# T35_8_CONNECTORS.net
KiCad netlist of a schematic drawn in Altium Designer
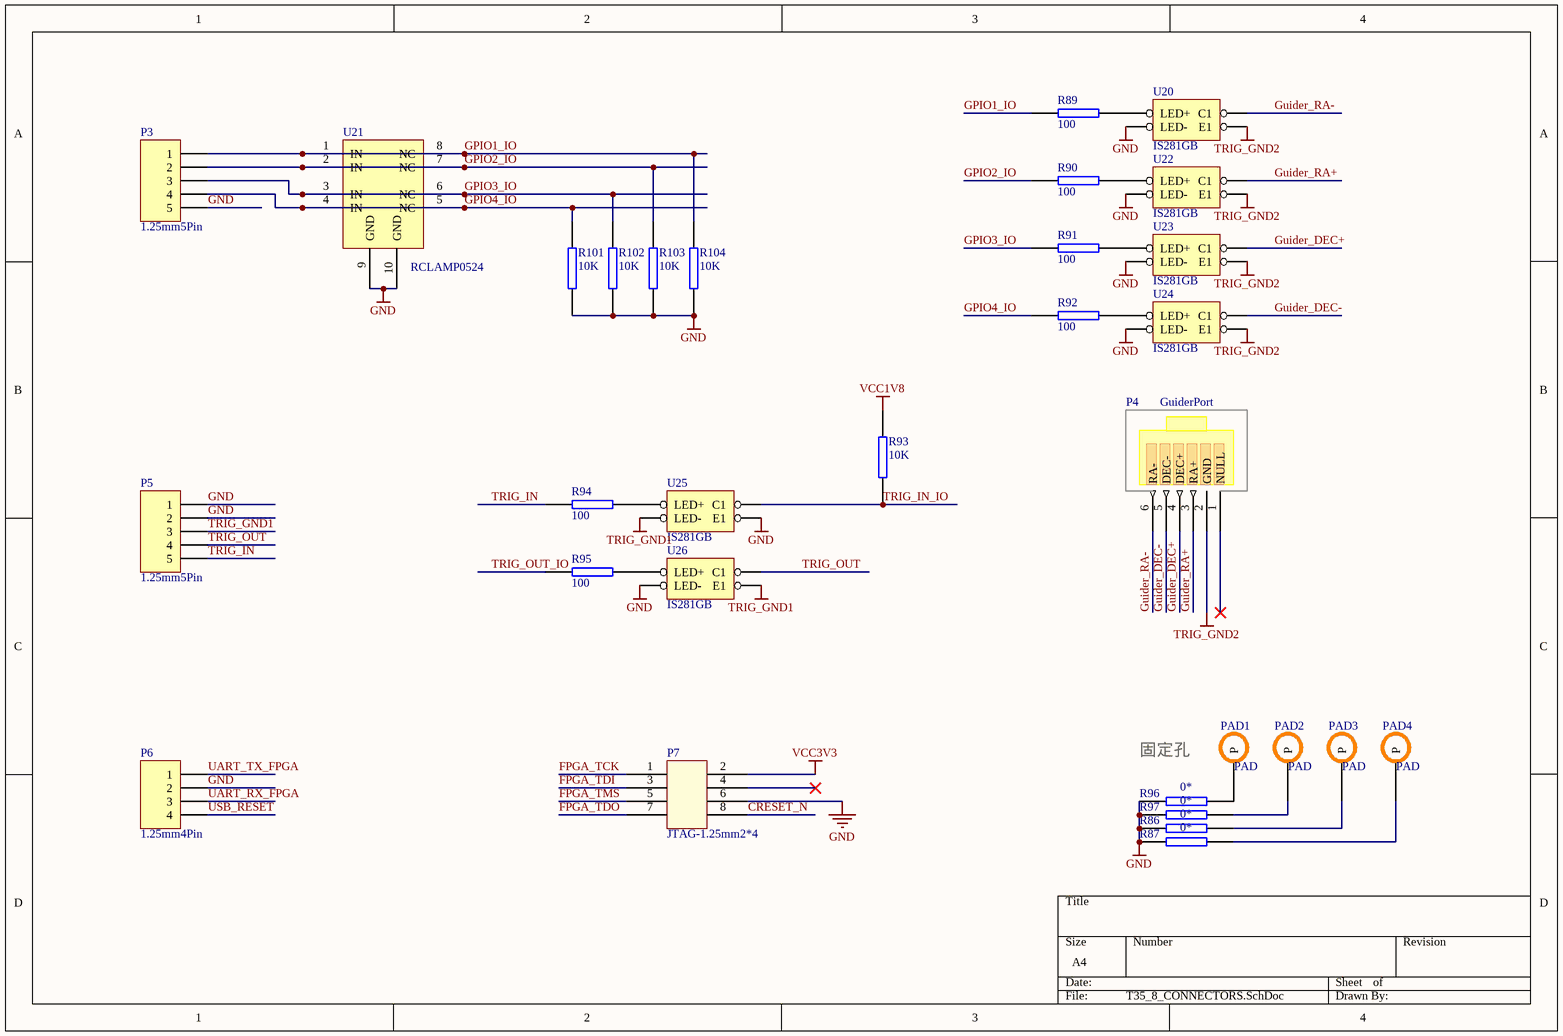
[diagram p0: T35_8_CONNECTORS.SchDoc]

(export (version "E")
  (design (tool "Eeschema 10.0.6"))
  (components
    (comp (ref "P3")
      (value "1.25mm5Pin")
      (footprint "CC125-5")
      (description "1.25mm间距5Pin插座")
      (fields (field (name "PUBLISHER") "Altium Limited"))
      (libsource (lib "Miscellaneous Connectors") (part "Header 5"))
    )
    (comp (ref "P4")
      (value "GuiderPort")
      (footprint "RJ11-SMD")
      (description "导星口RJ11")
      (libsource (lib "T35-V2") (part "GuiderPort"))
    )
    (comp (ref "P5")
      (value "1.25mm5Pin")
      (footprint "CC125-5")
      (description "1.25mm间距5Pin插座")
      (fields (field (name "PUBLISHER") "Altium Limited"))
      (libsource (lib "Miscellaneous Connectors") (part "Header 5"))
    )
    (comp (ref "P6")
      (value "1.25mm4Pin")
      (footprint "CON_530470410_MOL")
      (description "1.25mm间距4Pin插座")
      (libsource (lib "T35") (part "Con_4"))
    )
    (comp (ref "P7")
      (value "JTAG-1.25mm2*4")
      (footprint "MHDR2X4")
      (description "1.25mm间距2*4 8PinJTAG烧写座")
      (libsource (lib "T35-V2") (part "1.27mm2*4JTAGSocket"))
    )
    (comp (ref "PAD1")
      (value "PAD")
      (footprint "M2-R4-NC")
      (description "固定孔")
      (libsource (lib "QHY_LIB_SCH_AD10") (part "PAD"))
    )
    (comp (ref "PAD2")
      (value "PAD")
      (footprint "M2-R4-NC")
      (description "固定孔")
      (libsource (lib "QHY_LIB_SCH_AD10") (part "PAD"))
    )
    (comp (ref "PAD3")
      (value "PAD")
      (footprint "M1.6-R3.2-NC")
      (description "固定孔")
      (libsource (lib "QHY_LIB_SCH_AD10") (part "PAD"))
    )
    (comp (ref "PAD4")
      (value "PAD")
      (footprint "M1.6-R3.2-NC")
      (description "固定孔")
      (libsource (lib "QHY_LIB_SCH_AD10") (part "PAD"))
    )
    (comp (ref "R86")
      (value "0*")
      (footprint "0402RS")
      (description "贴片电阻")
      (libsource (lib "*") (part "RES2"))
    )
    (comp (ref "R87")
      (value "0*")
      (footprint "0402RS")
      (description "贴片电阻")
      (libsource (lib "*") (part "RES2"))
    )
    (comp (ref "R89")
      (value "100")
      (footprint "0402RS")
      (description "贴片电阻")
      (libsource (lib "*") (part "RES2"))
    )
    (comp (ref "R90")
      (value "100")
      (footprint "0402RS")
      (description "贴片电阻")
      (libsource (lib "*") (part "RES2"))
    )
    (comp (ref "R91")
      (value "100")
      (footprint "0402RS")
      (description "贴片电阻")
      (libsource (lib "*") (part "RES2"))
    )
    (comp (ref "R92")
      (value "100")
      (footprint "0402RS")
      (description "贴片电阻")
      (libsource (lib "*") (part "RES2"))
    )
    (comp (ref "R93")
      (value "10K")
      (footprint "0201RS")
      (description "贴片电阻")
      (libsource (lib "*") (part "RES2"))
    )
    (comp (ref "R94")
      (value "100")
      (footprint "0402RS")
      (description "贴片电阻")
      (libsource (lib "*") (part "RES2"))
    )
    (comp (ref "R95")
      (value "100")
      (footprint "0402RS")
      (description "贴片电阻")
      (libsource (lib "*") (part "RES2"))
    )
    (comp (ref "R96")
      (value "0*")
      (footprint "0402RS")
      (description "贴片电阻")
      (libsource (lib "*") (part "RES2"))
    )
    (comp (ref "R97")
      (value "0*")
      (footprint "0402RS")
      (description "贴片电阻")
      (libsource (lib "*") (part "RES2"))
    )
    (comp (ref "R101")
      (value "10K")
      (footprint "0201RS")
      (description "贴片电阻")
      (libsource (lib "*") (part "RES2"))
    )
    (comp (ref "R102")
      (value "10K")
      (footprint "0201RS")
      (description "贴片电阻")
      (libsource (lib "*") (part "RES2"))
    )
    (comp (ref "R103")
      (value "10K")
      (footprint "0201RS")
      (description "贴片电阻")
      (libsource (lib "*") (part "RES2"))
    )
    (comp (ref "R104")
      (value "10K")
      (footprint "0201RS")
      (description "贴片电阻")
      (libsource (lib "*") (part "RES2"))
    )
    (comp (ref "U20")
      (value "IS281GB")
      (footprint "TLP281-1")
      (description "光耦")
      (libsource (lib "QHY_SCHLIB") (part "TLP281_1"))
    )
    (comp (ref "U21")
      (value "RCLAMP0524")
      (footprint "RCLAMP0524")
      (description "ESD保护器件")
      (libsource (lib "QHY_SCHLIB") (part "RCLAMP0524"))
    )
    (comp (ref "U22")
      (value "IS281GB")
      (footprint "TLP281-1")
      (description "光耦")
      (libsource (lib "QHY_SCHLIB") (part "TLP281_1"))
    )
    (comp (ref "U23")
      (value "IS281GB")
      (footprint "TLP281-1")
      (description "光耦")
      (libsource (lib "QHY_SCHLIB") (part "TLP281_1"))
    )
    (comp (ref "U24")
      (value "IS281GB")
      (footprint "TLP281-1")
      (description "光耦")
      (libsource (lib "QHY_SCHLIB") (part "TLP281_1"))
    )
    (comp (ref "U25")
      (value "IS281GB")
      (footprint "TLP281-1")
      (description "光耦")
      (libsource (lib "QHY_SCHLIB") (part "TLP281_1"))
    )
    (comp (ref "U26")
      (value "IS281GB")
      (footprint "TLP281-1")
      (description "光耦")
      (libsource (lib "QHY_SCHLIB") (part "TLP281_1"))
    )
  )
  (nets
    (net (code "1") (name "/CRESET_N") (class "Default") (node (ref "P7") (pin "8") (pintype "passive")))
    (net (code "2") (name "/FPGA_TCK") (class "Default") (node (ref "P7") (pin "1") (pintype "passive")))
    (net (code "3") (name "/FPGA_TDI") (class "Default") (node (ref "P7") (pin "3") (pintype "passive")))
    (net (code "4") (name "/FPGA_TDO") (class "Default") (node (ref "P7") (pin "7") (pintype "passive")))
    (net (code "5") (name "/FPGA_TMS") (class "Default") (node (ref "P7") (pin "5") (pintype "passive")))
    (net (code "6") (name "/GPIO1_IO") (class "Default")
      (node (ref "P3") (pin "1") (pinfunction "1_1") (pintype "passive"))
      (node (ref "R104") (pin "1") (pinfunction "1_1") (pintype "passive"))
      (node (ref "R89") (pin "2") (pinfunction "2_2") (pintype "passive"))
      (node (ref "U21") (pin "1") (pinfunction "IN_1") (pintype "passive"))
      (node (ref "U21") (pin "8") (pinfunction "NC_8") (pintype "passive"))
    )
    (net (code "7") (name "/GPIO2_IO") (class "Default")
      (node (ref "P3") (pin "2") (pinfunction "2_2") (pintype "passive"))
      (node (ref "R103") (pin "1") (pinfunction "1_1") (pintype "passive"))
      (node (ref "R90") (pin "2") (pinfunction "2_2") (pintype "passive"))
      (node (ref "U21") (pin "2") (pinfunction "IN_2") (pintype "passive"))
      (node (ref "U21") (pin "7") (pinfunction "NC_7") (pintype "passive"))
    )
    (net (code "8") (name "/GPIO3_IO") (class "Default")
      (node (ref "P3") (pin "3") (pinfunction "3_3") (pintype "passive"))
      (node (ref "R102") (pin "1") (pinfunction "1_1") (pintype "passive"))
      (node (ref "R91") (pin "2") (pinfunction "2_2") (pintype "passive"))
      (node (ref "U21") (pin "3") (pinfunction "IN_3") (pintype "passive"))
      (node (ref "U21") (pin "6") (pinfunction "NC_6") (pintype "passive"))
    )
    (net (code "9") (name "/GPIO4_IO") (class "Default")
      (node (ref "P3") (pin "4") (pinfunction "4_4") (pintype "passive"))
      (node (ref "R101") (pin "1") (pinfunction "1_1") (pintype "passive"))
      (node (ref "R92") (pin "2") (pinfunction "2_2") (pintype "passive"))
      (node (ref "U21") (pin "4") (pinfunction "IN_4") (pintype "passive"))
      (node (ref "U21") (pin "5") (pinfunction "NC_5") (pintype "passive"))
    )
    (net (code "10") (name "/Guider_DEC+") (class "Default")
      (node (ref "P4") (pin "4") (pinfunction "DEC+_4") (pintype "output"))
      (node (ref "U23") (pin "4") (pinfunction "C1_4") (pintype "passive"))
    )
    (net (code "11") (name "/Guider_DEC-") (class "Default")
      (node (ref "P4") (pin "5") (pinfunction "DEC-_5") (pintype "output"))
      (node (ref "U24") (pin "4") (pinfunction "C1_4") (pintype "passive"))
    )
    (net (code "12") (name "/Guider_RA+") (class "Default")
      (node (ref "P4") (pin "3") (pinfunction "RA+_3") (pintype "output"))
      (node (ref "U22") (pin "4") (pinfunction "C1_4") (pintype "passive"))
    )
    (net (code "13") (name "/Guider_RA-") (class "Default")
      (node (ref "P4") (pin "6") (pinfunction "RA-_6") (pintype "output"))
      (node (ref "U20") (pin "4") (pinfunction "C1_4") (pintype "passive"))
    )
    (net (code "14") (name "/TRIG_IN") (class "Default")
      (node (ref "P5") (pin "5") (pinfunction "5_5") (pintype "passive"))
      (node (ref "R94") (pin "2") (pinfunction "2_2") (pintype "passive"))
    )
    (net (code "15") (name "/TRIG_IN_IO") (class "Default")
      (node (ref "R93") (pin "2") (pinfunction "2_2") (pintype "passive"))
      (node (ref "U25") (pin "4") (pinfunction "C1_4") (pintype "passive"))
    )
    (net (code "16") (name "/TRIG_OUT") (class "Default")
      (node (ref "P5") (pin "4") (pinfunction "4_4") (pintype "passive"))
      (node (ref "U26") (pin "4") (pinfunction "C1_4") (pintype "passive"))
    )
    (net (code "17") (name "/TRIG_OUT_IO") (class "Default")
      (node (ref "R95") (pin "2") (pinfunction "2_2") (pintype "passive"))
    )
    (net (code "18") (name "/UART_RX_FPGA") (class "Default")
      (node (ref "P6") (pin "3") (pinfunction "3_3") (pintype "passive"))
    )
    (net (code "19") (name "/UART_TX_FPGA") (class "Default")
      (node (ref "P6") (pin "1") (pinfunction "1_1") (pintype "passive"))
    )
    (net (code "20") (name "/USB_RESET") (class "Default")
      (node (ref "P6") (pin "4") (pinfunction "4_4") (pintype "passive"))
    )
    (net (code "21") (name "GND") (class "Default")
      (node (ref "P3") (pin "5") (pinfunction "5_5") (pintype "passive"))
      (node (ref "P5") (pin "1") (pinfunction "1_1") (pintype "passive"))
      (node (ref "P5") (pin "2") (pinfunction "2_2") (pintype "passive"))
      (node (ref "P6") (pin "2") (pinfunction "2_2") (pintype "passive"))
      (node (ref "P7") (pin "6") (pintype "passive"))
      (node (ref "R101") (pin "2") (pinfunction "2_2") (pintype "passive"))
      (node (ref "R102") (pin "2") (pinfunction "2_2") (pintype "passive"))
      (node (ref "R103") (pin "2") (pinfunction "2_2") (pintype "passive"))
      (node (ref "R104") (pin "2") (pinfunction "2_2") (pintype "passive"))
      (node (ref "R86") (pin "1") (pinfunction "1_1") (pintype "passive"))
      (node (ref "R87") (pin "1") (pinfunction "1_1") (pintype "passive"))
      (node (ref "R96") (pin "1") (pinfunction "1_1") (pintype "passive"))
      (node (ref "R97") (pin "1") (pinfunction "1_1") (pintype "passive"))
      (node (ref "U20") (pin "2") (pinfunction "LED-_2") (pintype "passive"))
      (node (ref "U21") (pin "10") (pinfunction "GND_10") (pintype "passive"))
      (node (ref "U21") (pin "9") (pinfunction "GND_9") (pintype "passive"))
      (node (ref "U22") (pin "2") (pinfunction "LED-_2") (pintype "passive"))
      (node (ref "U23") (pin "2") (pinfunction "LED-_2") (pintype "passive"))
      (node (ref "U24") (pin "2") (pinfunction "LED-_2") (pintype "passive"))
      (node (ref "U25") (pin "3") (pinfunction "E1_3") (pintype "passive"))
      (node (ref "U26") (pin "2") (pinfunction "LED-_2") (pintype "passive"))
    )
    (net (code "22") (name "Net-(PAD1-P)") (class "Default")
      (node (ref "PAD1") (pin "1") (pinfunction "P_1") (pintype "passive"))
      (node (ref "R96") (pin "2") (pinfunction "2_2") (pintype "passive"))
    )
    (net (code "23") (name "Net-(PAD2-P)") (class "Default")
      (node (ref "PAD2") (pin "1") (pinfunction "P_1") (pintype "passive"))
      (node (ref "R97") (pin "2") (pinfunction "2_2") (pintype "passive"))
    )
    (net (code "24") (name "Net-(PAD3-P)") (class "Default")
      (node (ref "PAD3") (pin "1") (pinfunction "P_1") (pintype "passive"))
      (node (ref "R86") (pin "2") (pinfunction "2_2") (pintype "passive"))
    )
    (net (code "25") (name "Net-(PAD4-P)") (class "Default")
      (node (ref "PAD4") (pin "1") (pinfunction "P_1") (pintype "passive"))
      (node (ref "R87") (pin "2") (pinfunction "2_2") (pintype "passive"))
    )
    (net (code "26") (name "Net-(U20-LED+)") (class "Default")
      (node (ref "R89") (pin "1") (pinfunction "1_1") (pintype "passive"))
      (node (ref "U20") (pin "1") (pinfunction "LED+_1") (pintype "passive"))
    )
    (net (code "27") (name "Net-(U22-LED+)") (class "Default")
      (node (ref "R90") (pin "1") (pinfunction "1_1") (pintype "passive"))
      (node (ref "U22") (pin "1") (pinfunction "LED+_1") (pintype "passive"))
    )
    (net (code "28") (name "Net-(U23-LED+)") (class "Default")
      (node (ref "R91") (pin "1") (pinfunction "1_1") (pintype "passive"))
      (node (ref "U23") (pin "1") (pinfunction "LED+_1") (pintype "passive"))
    )
    (net (code "29") (name "Net-(U24-LED+)") (class "Default")
      (node (ref "R92") (pin "1") (pinfunction "1_1") (pintype "passive"))
      (node (ref "U24") (pin "1") (pinfunction "LED+_1") (pintype "passive"))
    )
    (net (code "30") (name "Net-(U25-LED+)") (class "Default")
      (node (ref "R94") (pin "1") (pinfunction "1_1") (pintype "passive"))
      (node (ref "U25") (pin "1") (pinfunction "LED+_1") (pintype "passive"))
    )
    (net (code "31") (name "Net-(U26-LED+)") (class "Default")
      (node (ref "R95") (pin "1") (pinfunction "1_1") (pintype "passive"))
      (node (ref "U26") (pin "1") (pinfunction "LED+_1") (pintype "passive"))
    )
    (net (code "32") (name "TRIG_GND1") (class "Default")
      (node (ref "P5") (pin "3") (pinfunction "3_3") (pintype "passive"))
      (node (ref "U25") (pin "2") (pinfunction "LED-_2") (pintype "passive"))
      (node (ref "U26") (pin "3") (pinfunction "E1_3") (pintype "passive"))
    )
    (net (code "33") (name "TRIG_GND2") (class "Default")
      (node (ref "P4") (pin "2") (pinfunction "GND_2") (pintype "power_in"))
      (node (ref "U20") (pin "3") (pinfunction "E1_3") (pintype "passive"))
      (node (ref "U22") (pin "3") (pinfunction "E1_3") (pintype "passive"))
      (node (ref "U23") (pin "3") (pinfunction "E1_3") (pintype "passive"))
      (node (ref "U24") (pin "3") (pinfunction "E1_3") (pintype "passive"))
    )
    (net (code "34") (name "VCC1V8") (class "Default")
      (node (ref "R93") (pin "1") (pinfunction "1_1") (pintype "passive"))
    )
    (net (code "35") (name "VCC3V3") (class "Default") (node (ref "P7") (pin "2") (pintype "passive")))
    (net (code "36") (name "unconnected-(P4-NULL-Pad1)") (class "Default")
      (node (ref "P4") (pin "1") (pinfunction "NULL_1") (pintype "passive+no_connect"))
    )
    (net (code "37") (name "unconnected-(P7-Pad4)") (class "Default")
      (node (ref "P7") (pin "4") (pintype "passive+no_connect"))
    )
  )
)
